# test_strip_v0_1.net
KiCad netlist of a schematic drawn in EAGLE
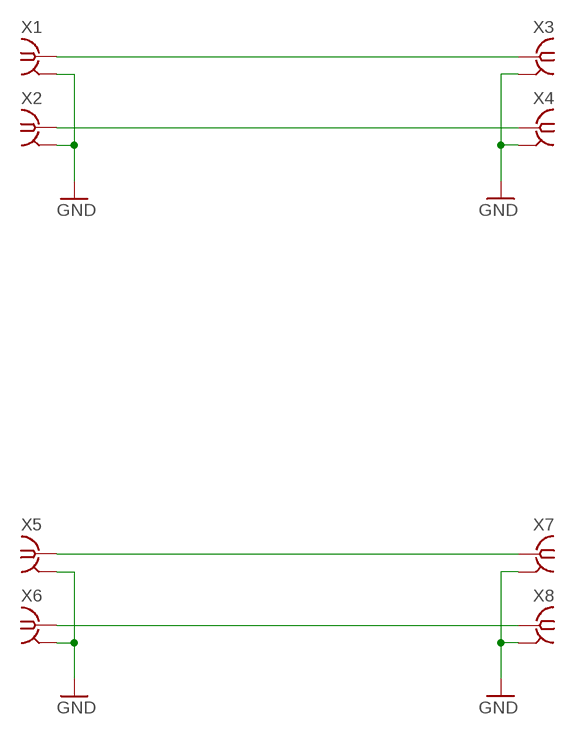
[diagram p0: schematic, sheet 1]

(export (version "E")
  (design (tool "Eeschema 10.0.6"))
  (components
    (comp (ref "X1")
      (value "BU-SMA-E-ND")
      (footprint "eagle-import:SMA-EDGE_ND")
      (libsource (lib "eagle-import") (part "BU-SMA-E-ND"))
    )
    (comp (ref "X2")
      (value "BU-SMA-E-ND")
      (footprint "eagle-import:SMA-EDGE_ND")
      (libsource (lib "eagle-import") (part "BU-SMA-E-ND"))
    )
    (comp (ref "X3")
      (value "BU-SMA-E-ND")
      (footprint "eagle-import:SMA-EDGE_ND")
      (libsource (lib "eagle-import") (part "BU-SMA-E-ND"))
    )
    (comp (ref "X4")
      (value "BU-SMA-E-ND")
      (footprint "eagle-import:SMA-EDGE_ND")
      (libsource (lib "eagle-import") (part "BU-SMA-E-ND"))
    )
    (comp (ref "X5")
      (value "BU-SMA-E-ND")
      (footprint "eagle-import:SMA-EDGE_ND")
      (libsource (lib "eagle-import") (part "BU-SMA-E-ND"))
    )
    (comp (ref "X6")
      (value "BU-SMA-E-ND")
      (footprint "eagle-import:SMA-EDGE_ND")
      (libsource (lib "eagle-import") (part "BU-SMA-E-ND"))
    )
    (comp (ref "X7")
      (value "BU-SMA-E-ND")
      (footprint "eagle-import:SMA-EDGE_ND")
      (libsource (lib "eagle-import") (part "BU-SMA-E-ND"))
    )
    (comp (ref "X8")
      (value "BU-SMA-E-ND")
      (footprint "eagle-import:SMA-EDGE_ND")
      (libsource (lib "eagle-import") (part "BU-SMA-E-ND"))
    )
  )
  (nets
    (net (code "1") (name "GND") (class "Default")
      (node (ref "X1") (pin "2@3") (pinfunction "2_2@3") (pintype "passive"))
      (node (ref "X1") (pin "2@4") (pinfunction "2_2@4") (pintype "passive"))
      (node (ref "X2") (pin "2@3") (pinfunction "2_2@3") (pintype "passive"))
      (node (ref "X2") (pin "2@4") (pinfunction "2_2@4") (pintype "passive"))
      (node (ref "X3") (pin "2@3") (pinfunction "2_2@3") (pintype "passive"))
      (node (ref "X3") (pin "2@4") (pinfunction "2_2@4") (pintype "passive"))
      (node (ref "X4") (pin "2@3") (pinfunction "2_2@3") (pintype "passive"))
      (node (ref "X4") (pin "2@4") (pinfunction "2_2@4") (pintype "passive"))
      (node (ref "X5") (pin "2@3") (pinfunction "2_2@3") (pintype "passive"))
      (node (ref "X5") (pin "2@4") (pinfunction "2_2@4") (pintype "passive"))
      (node (ref "X6") (pin "2@3") (pinfunction "2_2@3") (pintype "passive"))
      (node (ref "X6") (pin "2@4") (pinfunction "2_2@4") (pintype "passive"))
      (node (ref "X7") (pin "2@3") (pinfunction "2_2@3") (pintype "passive"))
      (node (ref "X7") (pin "2@4") (pinfunction "2_2@4") (pintype "passive"))
      (node (ref "X8") (pin "2@3") (pinfunction "2_2@3") (pintype "passive"))
      (node (ref "X8") (pin "2@4") (pinfunction "2_2@4") (pintype "passive"))
    )
    (net (code "2") (name "Net-(X1-Pad1)") (class "Default")
      (node (ref "X1") (pin "1") (pinfunction "1_1") (pintype "passive"))
      (node (ref "X3") (pin "1") (pinfunction "1_1") (pintype "passive"))
    )
    (net (code "3") (name "Net-(X2-Pad1)") (class "Default")
      (node (ref "X2") (pin "1") (pinfunction "1_1") (pintype "passive"))
      (node (ref "X4") (pin "1") (pinfunction "1_1") (pintype "passive"))
    )
    (net (code "4") (name "Net-(X5-Pad1)") (class "Default")
      (node (ref "X5") (pin "1") (pinfunction "1_1") (pintype "passive"))
      (node (ref "X7") (pin "1") (pinfunction "1_1") (pintype "passive"))
    )
    (net (code "5") (name "Net-(X6-Pad1)") (class "Default")
      (node (ref "X6") (pin "1") (pinfunction "1_1") (pintype "passive"))
      (node (ref "X8") (pin "1") (pinfunction "1_1") (pintype "passive"))
    )
  )
)
